# USB_DEBUG.net
KiCad netlist of a schematic drawn in Altium Designer
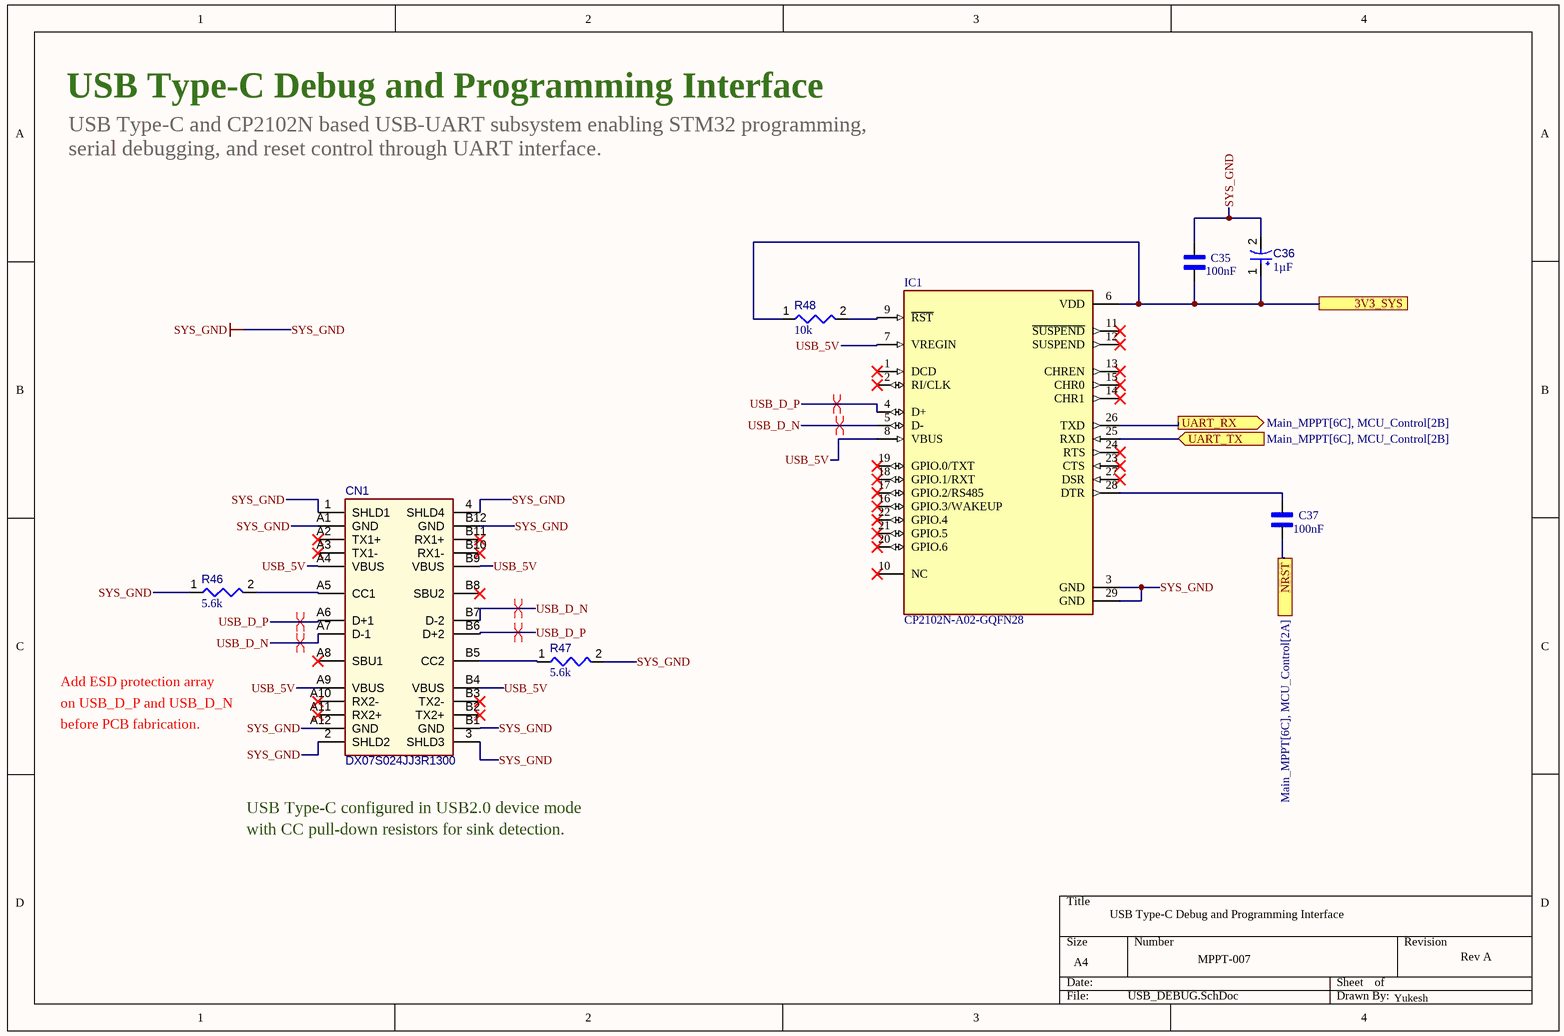
[diagram p0: USB_DEBUG.SchDoc]

(export (version "E")
  (design (tool "Eeschema 10.0.6"))
  (components
    (comp (ref "C35")
      (value "100nF")
      (footprint "CAPC1608X90N")
      (description "Capacitor MLCC 0603 100nF 16V")
      (fields (field (name "MP") "0603YC104KAZ2A") (field (name "MF") "AVX"))
      (libsource (lib "YUKESH S") (part "0603YC104KAZ2A"))
    )
    (comp (ref "C36")
      (value "1µF")
      (footprint "CAPMP3217X18-T_V")
      (description "Standard Tantalum, 1 uF, +/- 10%, 35 V, -55 to 125 degC, 1206 (3216 Metric), RoHS, Tape and Reel")
      (fields (field (name "TOLERANCE") "10%") (field (name "MANUFACTURER") "AVX"))
      (libsource (lib "YUKESH S") (part "CAP-P-2"))
    )
    (comp (ref "C37")
      (value "100nF")
      (footprint "CAPC1608X90N")
      (description "Capacitor MLCC 0603 100nF 16V")
      (fields (field (name "MP") "0603YC104KAZ2A") (field (name "MF") "AVX"))
      (libsource (lib "YUKESH S") (part "0603YC104KAZ2A"))
    )
    (comp (ref "CN1")
      (value "DX07S024JJ3R1300")
      (footprint "JAE-DX07S024JJ3_V")
      (description "USB-C Connector, 20 V, 1.25 A, -30 to 80 degC, RoHS, Tape and Reel")
      (libsource (lib "YUKESH S") (part "CMP-00171-5"))
    )
    (comp (ref "IC1")
      (value "CP2102N-A02-GQFN28")
      (footprint "QFN50P500X500X80-29N")
      (fields (field (name "MF") "Silicon Labs") (field (name "MP") "CP2102NA02GQFN28"))
      (libsource (lib "YUKESH S") (part "CP2102N-A02-GQFN28"))
    )
    (comp (ref "R46")
      (value "5.6k")
      (footprint "RESC0402(1005)_L")
      (description "5K6 0.063W 5% 0402 (1005 Metric)  SMD")
      (fields (field (name "TOLERANCE") "5%") (field (name "POWER") "63mW"))
      (libsource (lib "YUKESH S") (part "5D6KR2J"))
    )
    (comp (ref "R47")
      (value "5.6k")
      (footprint "RESC0402(1005)_L")
      (description "5K6 0.063W 5% 0402 (1005 Metric)  SMD")
      (fields (field (name "TOLERANCE") "5%") (field (name "POWER") "63mW"))
      (libsource (lib "YUKESH S") (part "5D6KR2J"))
    )
    (comp (ref "R48")
      (value "10k")
      (footprint "RESC0402(1005)_L")
      (description "10K 0.063W 1% 0402 (1005 Metric)  SMD")
      (fields (field (name "POWER") "63mW") (field (name "TOLERANCE") "1%"))
      (libsource (lib "YUKESH S") (part "10KR2F"))
    )
  )
  (nets
    (net (code "1") (name "/3V3_SYS") (class "Default")
      (node (ref "C35") (pin "1") (pinfunction "1_1") (pintype "passive"))
      (node (ref "C36") (pin "1") (pinfunction "1_1") (pintype "passive"))
      (node (ref "IC1") (pin "6") (pinfunction "VDD_6") (pintype "power_in"))
      (node (ref "R48") (pin "1") (pinfunction "1_1") (pintype "passive"))
    )
    (net (code "2") (name "/NRST") (class "Default")
      (node (ref "C37") (pin "1") (pinfunction "1_1") (pintype "passive"))
    )
    (net (code "3") (name "/UART_RX") (class "Default")
      (node (ref "IC1") (pin "26") (pinfunction "TXD_26") (pintype "output"))
    )
    (net (code "4") (name "/UART_TX") (class "Default")
      (node (ref "IC1") (pin "25") (pinfunction "RXD_25") (pintype "input"))
    )
    (net (code "5") (name "/USB_5V") (class "Default")
      (node (ref "CN1") (pin "A4") (pinfunction "VBUS_A4") (pintype "passive"))
      (node (ref "CN1") (pin "A9") (pinfunction "VBUS_A9") (pintype "passive"))
      (node (ref "CN1") (pin "B4") (pinfunction "VBUS_B4") (pintype "passive"))
      (node (ref "CN1") (pin "B9") (pinfunction "VBUS_B9") (pintype "passive"))
      (node (ref "IC1") (pin "7") (pinfunction "VREGIN_7") (pintype "input"))
      (node (ref "IC1") (pin "8") (pinfunction "VBUS_8") (pintype "input"))
    )
    (net (code "6") (name "/USB_D_N") (class "Default")
      (node (ref "CN1") (pin "A7") (pinfunction "D-1_A7") (pintype "passive"))
      (node (ref "CN1") (pin "B7") (pinfunction "D-2_B7") (pintype "passive"))
      (node (ref "IC1") (pin "5") (pinfunction "D-_5") (pintype "bidirectional"))
    )
    (net (code "7") (name "/USB_D_P") (class "Default")
      (node (ref "CN1") (pin "A6") (pinfunction "D+1_A6") (pintype "passive"))
      (node (ref "CN1") (pin "B6") (pinfunction "D+2_B6") (pintype "passive"))
      (node (ref "IC1") (pin "4") (pinfunction "D+_4") (pintype "bidirectional"))
    )
    (net (code "8") (name "Net-(CN1-CC1)") (class "Default")
      (node (ref "CN1") (pin "A5") (pinfunction "CC1_A5") (pintype "passive"))
      (node (ref "R46") (pin "2") (pinfunction "2_2") (pintype "passive"))
    )
    (net (code "9") (name "Net-(CN1-CC2)") (class "Default")
      (node (ref "CN1") (pin "B5") (pinfunction "CC2_B5") (pintype "passive"))
      (node (ref "R47") (pin "1") (pinfunction "1_1") (pintype "passive"))
    )
    (net (code "10") (name "Net-(IC1-DTR)") (class "Default")
      (node (ref "C37") (pin "2") (pinfunction "2_2") (pintype "passive"))
      (node (ref "IC1") (pin "28") (pinfunction "DTR_28") (pintype "output"))
    )
    (net (code "11") (name "Net-(IC1-~{RST})") (class "Default")
      (node (ref "IC1") (pin "9") (pinfunction "~{RST}_9") (pintype "input"))
      (node (ref "R48") (pin "2") (pinfunction "2_2") (pintype "passive"))
    )
    (net (code "12") (name "SYS_GND") (class "Default")
      (node (ref "C35") (pin "2") (pinfunction "2_2") (pintype "passive"))
      (node (ref "C36") (pin "2") (pinfunction "2_2") (pintype "passive"))
      (node (ref "CN1") (pin "1") (pinfunction "SHLD1_1") (pintype "passive"))
      (node (ref "CN1") (pin "2") (pinfunction "SHLD2_2") (pintype "passive"))
      (node (ref "CN1") (pin "3") (pinfunction "SHLD3_3") (pintype "passive"))
      (node (ref "CN1") (pin "4") (pinfunction "SHLD4_4") (pintype "passive"))
      (node (ref "CN1") (pin "A1") (pinfunction "GND_A1") (pintype "passive"))
      (node (ref "CN1") (pin "A12") (pinfunction "GND_A12") (pintype "passive"))
      (node (ref "CN1") (pin "B1") (pinfunction "GND_B1") (pintype "passive"))
      (node (ref "CN1") (pin "B12") (pinfunction "GND_B12") (pintype "passive"))
      (node (ref "IC1") (pin "29") (pinfunction "GND_29") (pintype "power_in"))
      (node (ref "IC1") (pin "3") (pinfunction "GND_3") (pintype "power_in"))
      (node (ref "R46") (pin "1") (pinfunction "1_1") (pintype "passive"))
      (node (ref "R47") (pin "2") (pinfunction "2_2") (pintype "passive"))
    )
    (net (code "13") (name "unconnected-(CN1-RX1+-PadB11)") (class "Default")
      (node (ref "CN1") (pin "B11") (pinfunction "RX1+_B11") (pintype "passive+no_connect"))
    )
    (net (code "14") (name "unconnected-(CN1-RX1--PadB10)") (class "Default")
      (node (ref "CN1") (pin "B10") (pinfunction "RX1-_B10") (pintype "passive+no_connect"))
    )
    (net (code "15") (name "unconnected-(CN1-RX2+-PadA11)") (class "Default")
      (node (ref "CN1") (pin "A11") (pinfunction "RX2+_A11") (pintype "passive+no_connect"))
    )
    (net (code "16") (name "unconnected-(CN1-RX2--PadA10)") (class "Default")
      (node (ref "CN1") (pin "A10") (pinfunction "RX2-_A10") (pintype "passive+no_connect"))
    )
    (net (code "17") (name "unconnected-(CN1-SBU1-PadA8)") (class "Default")
      (node (ref "CN1") (pin "A8") (pinfunction "SBU1_A8") (pintype "passive+no_connect"))
    )
    (net (code "18") (name "unconnected-(CN1-SBU2-PadB8)") (class "Default")
      (node (ref "CN1") (pin "B8") (pinfunction "SBU2_B8") (pintype "passive+no_connect"))
    )
    (net (code "19") (name "unconnected-(CN1-TX1+-PadA2)") (class "Default")
      (node (ref "CN1") (pin "A2") (pinfunction "TX1+_A2") (pintype "passive+no_connect"))
    )
    (net (code "20") (name "unconnected-(CN1-TX1--PadA3)") (class "Default")
      (node (ref "CN1") (pin "A3") (pinfunction "TX1-_A3") (pintype "passive+no_connect"))
    )
    (net (code "21") (name "unconnected-(CN1-TX2+-PadB2)") (class "Default")
      (node (ref "CN1") (pin "B2") (pinfunction "TX2+_B2") (pintype "passive+no_connect"))
    )
    (net (code "22") (name "unconnected-(CN1-TX2--PadB3)") (class "Default")
      (node (ref "CN1") (pin "B3") (pinfunction "TX2-_B3") (pintype "passive+no_connect"))
    )
    (net (code "23") (name "unconnected-(IC1-CHR0-Pad15)") (class "Default")
      (node (ref "IC1") (pin "15") (pinfunction "CHR0_15") (pintype "output+no_connect"))
    )
    (net (code "24") (name "unconnected-(IC1-CHR1-Pad14)") (class "Default")
      (node (ref "IC1") (pin "14") (pinfunction "CHR1_14") (pintype "output+no_connect"))
    )
    (net (code "25") (name "unconnected-(IC1-CHREN-Pad13)") (class "Default")
      (node (ref "IC1") (pin "13") (pinfunction "CHREN_13") (pintype "output+no_connect"))
    )
    (net (code "26") (name "unconnected-(IC1-CTS-Pad23)") (class "Default")
      (node (ref "IC1") (pin "23") (pinfunction "CTS_23") (pintype "input+no_connect"))
    )
    (net (code "27") (name "unconnected-(IC1-DCD-Pad1)") (class "Default")
      (node (ref "IC1") (pin "1") (pinfunction "DCD_1") (pintype "input+no_connect"))
    )
    (net (code "28") (name "unconnected-(IC1-DSR-Pad27)") (class "Default")
      (node (ref "IC1") (pin "27") (pinfunction "DSR_27") (pintype "input+no_connect"))
    )
    (net (code "29") (name "unconnected-(IC1-GPIO.0{slash}TXT-Pad19)") (class "Default")
      (node (ref "IC1") (pin "19") (pinfunction "GPIO.0/TXT_19") (pintype "bidirectional+no_connect"))
    )
    (net (code "30") (name "unconnected-(IC1-GPIO.1{slash}RXT-Pad18)") (class "Default")
      (node (ref "IC1") (pin "18") (pinfunction "GPIO.1/RXT_18") (pintype "bidirectional+no_connect"))
    )
    (net (code "31") (name "unconnected-(IC1-GPIO.2{slash}RS485-Pad17)") (class "Default")
      (node (ref "IC1") (pin "17") (pinfunction "GPIO.2/RS485_17") (pintype "bidirectional+no_connect"))
    )
    (net (code "32") (name "unconnected-(IC1-GPIO.3{slash}WAKEUP-Pad16)") (class "Default")
      (node (ref "IC1") (pin "16") (pinfunction "GPIO.3/WAKEUP_16") (pintype "bidirectional+no_connect"))
    )
    (net (code "33") (name "unconnected-(IC1-GPIO.4-Pad22)") (class "Default")
      (node (ref "IC1") (pin "22") (pinfunction "GPIO.4_22") (pintype "bidirectional+no_connect"))
    )
    (net (code "34") (name "unconnected-(IC1-GPIO.5-Pad21)") (class "Default")
      (node (ref "IC1") (pin "21") (pinfunction "GPIO.5_21") (pintype "bidirectional+no_connect"))
    )
    (net (code "35") (name "unconnected-(IC1-GPIO.6-Pad20)") (class "Default")
      (node (ref "IC1") (pin "20") (pinfunction "GPIO.6_20") (pintype "bidirectional+no_connect"))
    )
    (net (code "36") (name "unconnected-(IC1-NC-Pad10)") (class "Default")
      (node (ref "IC1") (pin "10") (pinfunction "NC_10") (pintype "passive+no_connect"))
    )
    (net (code "37") (name "unconnected-(IC1-RI{slash}CLK-Pad2)") (class "Default")
      (node (ref "IC1") (pin "2") (pinfunction "RI/CLK_2") (pintype "bidirectional+no_connect"))
    )
    (net (code "38") (name "unconnected-(IC1-RTS-Pad24)") (class "Default")
      (node (ref "IC1") (pin "24") (pinfunction "RTS_24") (pintype "output+no_connect"))
    )
    (net (code "39") (name "unconnected-(IC1-SUSPEND-Pad12)") (class "Default")
      (node (ref "IC1") (pin "12") (pinfunction "SUSPEND_12") (pintype "output+no_connect"))
    )
    (net (code "40") (name "unconnected-(IC1-~{SUSPEND}-Pad11)") (class "Default")
      (node (ref "IC1") (pin "11") (pinfunction "~{SUSPEND}_11") (pintype "output+no_connect"))
    )
  )
)
